# Main.net
KiCad netlist of a schematic drawn in Altium Designer
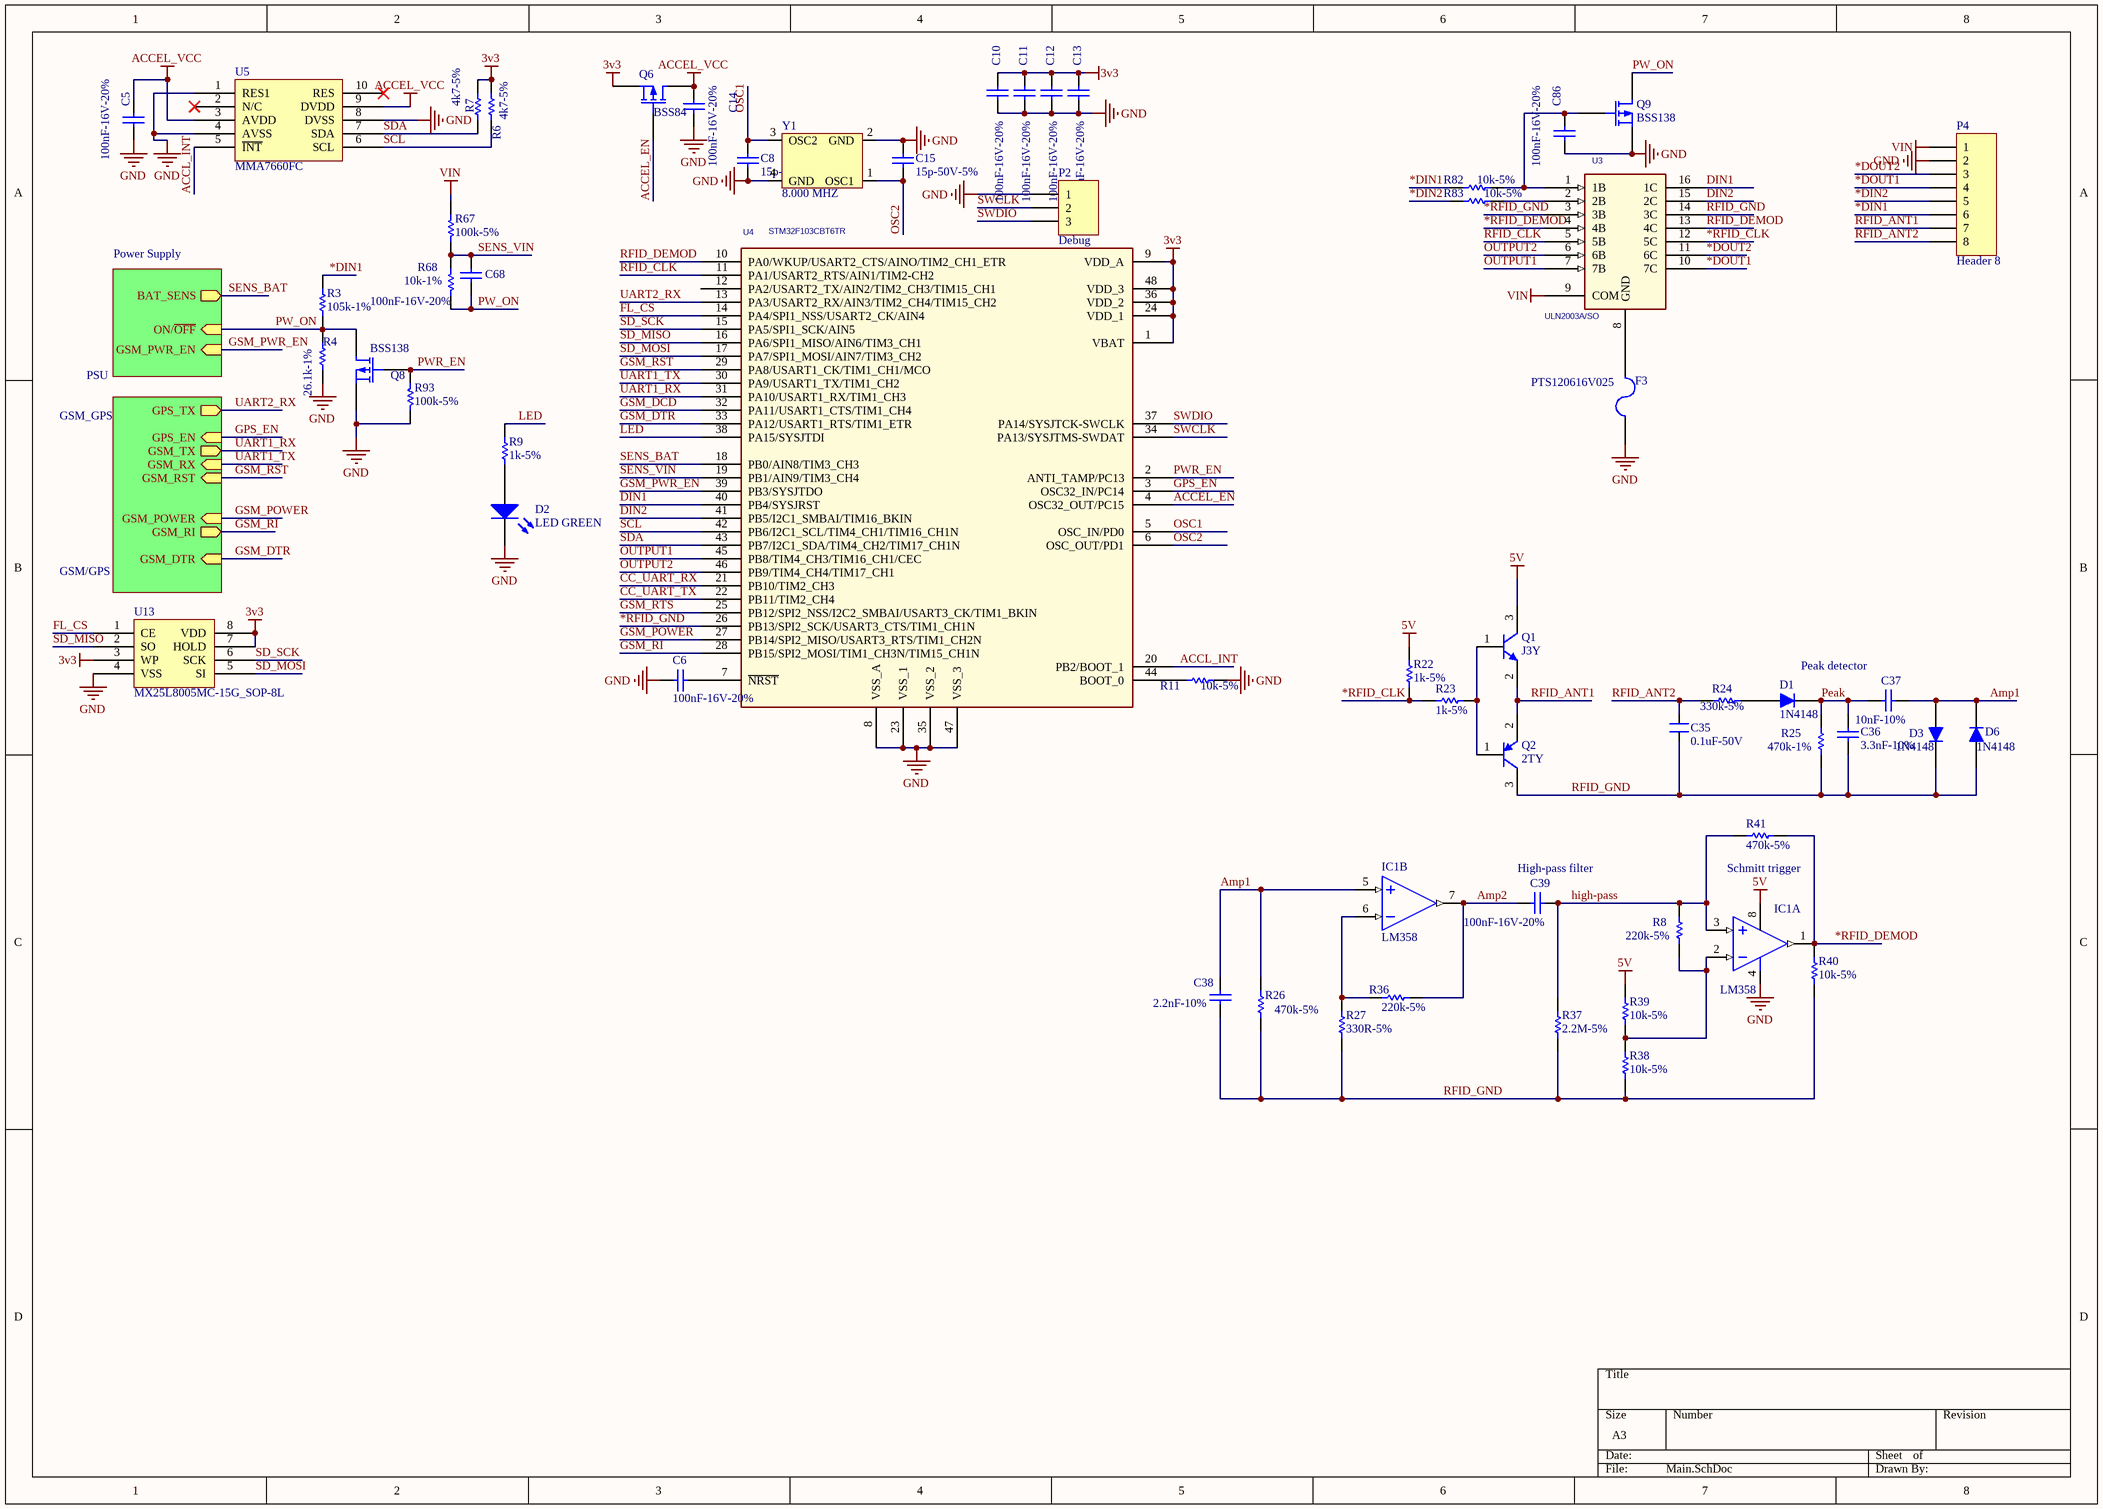
[diagram p0: Main.SchDoc]

(export (version "E")
  (design (tool "Eeschema 10.0.6"))
  (components
    (comp (ref "C5")
      (value "100nF-16V-20%")
      (footprint "C0402")
      (description "CAP CER 0.1UF 16V Y5V 0402")
      (fields
        (field (name "MANUFACTURER") "Yageo")
        (field (name "DIGI-KEY PART NUMBER") "311-1047-1-ND")
        (field (name "PUBLISHER") "Altium Limited")
      )
      (libsource (lib "Miscellaneous Devices") (part "Cap"))
    )
    (comp (ref "C6")
      (value "100nF-16V-20%")
      (footprint "C0402")
      (description "CAP CER 0.1UF 16V Y5V 0402")
      (fields
        (field (name "MANUFACTURER") "Yageo")
        (field (name "DIGI-KEY PART NUMBER") "311-1047-1-ND")
        (field (name "PUBLISHER") "Altium Limited")
      )
      (libsource (lib "Miscellaneous Devices") (part "Cap"))
    )
    (comp (ref "C8")
      (value "15p-50V-5%")
      (footprint "C0402")
      (description "CAP CER 15PF 50V 5% NPO 0402")
      (fields
        (field (name "MANUFACTURER") "Yageo")
        (field (name "DIGI-KEY PART NUMBER") "311-1017-1-ND")
        (field (name "PUBLISHER") "Altium Limited")
      )
      (libsource (lib "Miscellaneous Devices") (part "Cap"))
    )
    (comp (ref "C10")
      (value "100nF-16V-20%")
      (footprint "C0402")
      (description "CAP CER 0.1UF 16V Y5V 0402")
      (fields
        (field (name "MANUFACTURER") "Yageo")
        (field (name "DIGI-KEY PART NUMBER") "311-1047-1-ND")
        (field (name "PUBLISHER") "Altium Limited")
      )
      (libsource (lib "Miscellaneous Devices") (part "Cap"))
    )
    (comp (ref "C11")
      (value "100nF-16V-20%")
      (footprint "C0402")
      (description "CAP CER 0.1UF 16V Y5V 0402")
      (fields
        (field (name "MANUFACTURER") "Yageo")
        (field (name "DIGI-KEY PART NUMBER") "311-1047-1-ND")
        (field (name "PUBLISHER") "Altium Limited")
      )
      (libsource (lib "Miscellaneous Devices") (part "Cap"))
    )
    (comp (ref "C12")
      (value "100nF-16V-20%")
      (footprint "C0402")
      (description "CAP CER 0.1UF 16V Y5V 0402")
      (fields
        (field (name "MANUFACTURER") "Yageo")
        (field (name "DIGI-KEY PART NUMBER") "311-1047-1-ND")
        (field (name "PUBLISHER") "Altium Limited")
      )
      (libsource (lib "Miscellaneous Devices") (part "Cap"))
    )
    (comp (ref "C13")
      (value "100nF-16V-20%")
      (footprint "C0402")
      (description "CAP CER 0.1UF 16V Y5V 0402")
      (fields
        (field (name "MANUFACTURER") "Yageo")
        (field (name "DIGI-KEY PART NUMBER") "311-1047-1-ND")
        (field (name "PUBLISHER") "Altium Limited")
      )
      (libsource (lib "Miscellaneous Devices") (part "Cap"))
    )
    (comp (ref "C14")
      (value "100nF-16V-20%")
      (footprint "C0402")
      (description "CAP CER 0.1UF 16V Y5V 0402")
      (fields
        (field (name "MANUFACTURER") "Yageo")
        (field (name "DIGI-KEY PART NUMBER") "311-1047-1-ND")
        (field (name "PUBLISHER") "Altium Limited")
      )
      (libsource (lib "Miscellaneous Devices") (part "Cap"))
    )
    (comp (ref "C15")
      (value "15p-50V-5%")
      (footprint "C0402")
      (description "CAP CER 15PF 50V 5% NPO 0402")
      (fields
        (field (name "MANUFACTURER") "Yageo")
        (field (name "DIGI-KEY PART NUMBER") "311-1017-1-ND")
        (field (name "PUBLISHER") "Altium Limited")
      )
      (libsource (lib "Miscellaneous Devices") (part "Cap"))
    )
    (comp (ref "C35")
      (value "0.1uF-50V")
      (footprint "C0603")
      (description "CAP CER 0.1UF 50V Y5V 0603")
      (fields (field (name "DIGI-KEY PART NUMBER") "311-1343-2-ND") (field (name "MANUFACTURER") "Yageo"))
      (libsource (lib "syhaunguyen") (part "CN2"))
    )
    (comp (ref "C36")
      (value "3.3nF-10%")
      (footprint "C0402")
      (description "CAP CER 3300PF 50V 10% X7R 0402")
      (fields (field (name "DIGI-KEY PART NUMBER") "311-1034-2-ND") (field (name "MANUFACTURER") "Yageo"))
      (libsource (lib "Capacitor") (part "1nF-50V-C0805"))
    )
    (comp (ref "C37")
      (value "10nF-10%")
      (footprint "C0402")
      (description "Non-Polarized Capacitor")
      (fields (field (name "DIGI-KEY PART NUMBER") "CC0402KRX7R9BB103") (field (name "MANUFACTURER") "Yageo"))
      (libsource (lib "Capacitor") (part "10nF-50V-C0805"))
    )
    (comp (ref "C38")
      (value "2.2nF-10%")
      (footprint "C0402")
      (description "CAP CER 2200PF 50V 10% X7R 0402")
      (fields (field (name "DIGI-KEY PART NUMBER") "311-1037-2-ND") (field (name "MANUFACTURER") "Yageo"))
      (libsource (lib "Capacitor") (part "2.2nF-50V-C0805"))
    )
    (comp (ref "C39")
      (value "100nF-16V-20%")
      (footprint "C0402")
      (description "CAP CER 0.1UF 16V Y5V 0402")
      (fields
        (field (name "MANUFACTURER") "Yageo")
        (field (name "DIGI-KEY PART NUMBER") "311-1047-1-ND")
        (field (name "PUBLISHER") "Altium Limited")
      )
      (libsource (lib "Miscellaneous Devices") (part "Cap"))
    )
    (comp (ref "C68")
      (value "100nF-16V-20%")
      (footprint "C0402")
      (description "CAP CER 0.1UF 16V Y5V 0402")
      (fields
        (field (name "MANUFACTURER") "Yageo")
        (field (name "DIGI-KEY PART NUMBER") "311-1047-1-ND")
        (field (name "PUBLISHER") "Altium Limited")
      )
      (libsource (lib "Miscellaneous Devices") (part "Cap"))
    )
    (comp (ref "C86")
      (value "100nF-16V-20%")
      (footprint "C0402")
      (description "CAP CER 0.1UF 16V Y5V 0402")
      (fields
        (field (name "MANUFACTURER") "Yageo")
        (field (name "DIGI-KEY PART NUMBER") "311-1047-1-ND")
        (field (name "PUBLISHER") "Altium Limited")
      )
      (libsource (lib "Miscellaneous Devices") (part "Cap"))
    )
    (comp (ref "D1")
      (value "1N4148")
      (footprint "DO-213AA")
      (description "DIODE SMALL SIG 100V 0.2A ALF2")
      (fields
        (field (name "DIGI-KEY PART NUMBER") "568-1360-1-ND")
        (field (name "MANUFACTURER") "NXP Semiconductors")
      )
      (libsource (lib "Active Components") (part "1N4148"))
    )
    (comp (ref "D2")
      (value "LED GREEN")
      (footprint "LED0603-G")
      (description "LED GREEN CLEAR THIN 0603 SMD")
      (fields
        (field (name "DIGI-KEY PART NUMBER") "160-1446-2-ND")
        (field (name "MANUFACTURER") "Lite-On Inc")
        (field (name "PUBLISHER") "Altium Limited")
      )
      (libsource (lib "Miscellaneous Devices") (part "LED2"))
    )
    (comp (ref "D3")
      (value "1N4148")
      (footprint "DO-213AA")
      (description "DIODE SMALL SIG 100V 0.2A ALF2")
      (fields
        (field (name "DIGI-KEY PART NUMBER") "568-1360-1-ND")
        (field (name "MANUFACTURER") "NXP Semiconductors")
      )
      (libsource (lib "Active Components") (part "1N4148"))
    )
    (comp (ref "D6")
      (value "1N4148")
      (footprint "DO-213AA")
      (description "DIODE SMALL SIG 100V 0.2A ALF2")
      (fields
        (field (name "DIGI-KEY PART NUMBER") "568-1360-1-ND")
        (field (name "MANUFACTURER") "NXP Semiconductors")
      )
      (libsource (lib "Active Components") (part "1N4148"))
    )
    (comp (ref "F3")
      (value "PTS120616V025")
      (footprint "PTC1206")
      (description "PTC RESETTABLE SMD 1206 16V .25A")
      (fields
        (field (name "DIGI-KEY PART NUMBER") "283-3137-2-ND")
        (field (name "MANUFACTURER") "Cooper Bussmann")
        (field (name "PUBLISHER") "Altium Limited")
      )
      (libsource (lib "Miscellaneous Devices") (part "Fuse 2"))
    )
    (comp (ref "IC1")
      (value "LM358")
      (footprint "soic8")
      (description "Low-Power Dual Operational Amplifier")
      (libsource (lib "IC") (part "LM358"))
    )
    (comp (ref "P2")
      (value "Debug")
      (footprint "HEADER_1.27mm_3PIN")
      (description "NA")
      (fields (field (name "PUBLISHER") "Altium Limited"))
      (libsource (lib "Miscellaneous Connectors") (part "Header 3"))
    )
    (comp (ref "P4")
      (value "Header 8")
      (footprint "HDR1X8")
      (description "Header, 8-Pin")
      (fields (field (name "PUBLISHER") "Altium Limited"))
      (libsource (lib "Miscellaneous Connectors") (part "Header 8"))
    )
    (comp (ref "Q1")
      (value "J3Y")
      (footprint "SOT23_123")
      (description "NPN Bipolar Transistor")
      (libsource (lib "Active Components") (part "NPN_123"))
    )
    (comp (ref "Q2")
      (value "2TY")
      (footprint "SOT23_123")
      (description "PNP Bipolar Transistor")
      (libsource (lib "Active Components") (part "PNP_123"))
    )
    (comp (ref "Q6")
      (value "BSS84")
      (footprint "SOT23-3")
      (description "MOSFET P-CH 50V 130MA SOT23-3")
      (fields
        (field (name "DIGI-KEY PART NUMBER") "BSS84-FDITR-ND")
        (field (name "MANUFACTURER") "Diodes Inc")
        (field (name "PUBLISHER") "Altium Limited")
      )
      (libsource (lib "Miscellaneous Devices") (part "MOSFET-P"))
    )
    (comp (ref "Q8")
      (value "BSS138")
      (footprint "SOT23-3")
      (description "MOSFET N-CH 50V 200MA SOT23-3")
      (fields
        (field (name "DIGI-KEY PART NUMBER") "BSS138-FDICT-ND")
        (field (name "MANUFACTURER") "Diodes Inc")
        (field (name "PUBLISHER") "Altium Limited")
      )
      (libsource (lib "") (part "MOSFET-P_1"))
    )
    (comp (ref "Q9")
      (value "BSS138")
      (footprint "SOT23-3")
      (description "MOSFET N-CH 50V 200MA SOT23-3")
      (fields
        (field (name "DIGI-KEY PART NUMBER") "BSS138-FDICT-ND")
        (field (name "MANUFACTURER") "Diodes Inc")
        (field (name "PUBLISHER") "Altium Limited")
      )
      (libsource (lib "") (part "MOSFET-P_1"))
    )
    (comp (ref "R3")
      (value "105k-1%")
      (footprint "R0402")
      (description "RES 105k OHM 1/4W 1% 0805 SMD")
      (fields (field (name "DIGI-KEY PART NUMBER") "311-105KCRTR-ND") (field (name "MANUFACTURER") "Yageo"))
      (libsource (lib "All_Resistor") (part "105k-1%-R0805"))
    )
    (comp (ref "R4")
      (value "26.1k-1%")
      (footprint "R0402")
      (description "RES 26.1k OHM 1/4W 1% 0805 SMD")
      (fields (field (name "DIGI-KEY PART NUMBER") "311-26.1KCRTR-ND") (field (name "MANUFACTURER") "Yageo"))
      (libsource (lib "All_Resistor") (part "26.1k-1%-R0805"))
    )
    (comp (ref "R6")
      (value "4k7-5%")
      (footprint "R0402")
      (description "RES 4.7K OHM 1/16W 5% 0402 SMD")
      (fields
        (field (name "DIGI-KEY PART NUMBER") "311-4.7KJRCT-ND")
        (field (name "MANUFACTURER") "Yageo")
        (field (name "PUBLISHER") "Altium Limited")
      )
      (libsource (lib "Miscellaneous Devices") (part "Res1"))
    )
    (comp (ref "R7")
      (value "4k7-5%")
      (footprint "R0402")
      (description "RES 4.7K OHM 1/16W 5% 0402 SMD")
      (fields
        (field (name "DIGI-KEY PART NUMBER") "311-4.7KJRCT-ND")
        (field (name "MANUFACTURER") "Yageo")
        (field (name "PUBLISHER") "Altium Limited")
      )
      (libsource (lib "Miscellaneous Devices") (part "Res1"))
    )
    (comp (ref "R8")
      (value "220k-5%")
      (footprint "R0402")
      (description "RES 220k OHM 1/8W 5% 0805 SMD")
      (fields (field (name "DIGI-KEY PART NUMBER") "311-220KARTR-ND") (field (name "MANUFACTURER") "Yageo"))
      (libsource (lib "Resistor") (part "220k-5%-R0805"))
    )
    (comp (ref "R9")
      (value "1k-5%")
      (footprint "R0402")
      (description "RES 1.0K OHM 1/16W 5% 0402 SMD")
      (fields
        (field (name "DIGI-KEY PART NUMBER") "311-1.0KJRCT-ND")
        (field (name "MANUFACTURER") "Yageo")
        (field (name "PUBLISHER") "Altium Limited")
      )
      (libsource (lib "Miscellaneous Devices") (part "Res1"))
    )
    (comp (ref "R11")
      (value "10k-5%")
      (footprint "R0402")
      (description "RES 10K OHM 1/16W 5% 0402 SMD")
      (fields
        (field (name "DIGI-KEY PART NUMBER") "311-10KJRCT-ND")
        (field (name "MANUFACTURER") "Yageo")
        (field (name "PUBLISHER") "Altium Limited")
      )
      (libsource (lib "Miscellaneous Devices") (part "Res1"))
    )
    (comp (ref "R22")
      (value "1k-5%")
      (footprint "R0402")
      (description "RES 1k OHM 1/8W 5% 0805 SMD")
      (fields (field (name "DIGI-KEY PART NUMBER") "311-1.0KARTR-ND") (field (name "MANUFACTURER") "Yageo"))
      (libsource (lib "All_Resistor") (part "1k-5%-R0805"))
    )
    (comp (ref "R23")
      (value "1k-5%")
      (footprint "R0402")
      (description "RES 1k OHM 1/8W 5% 0805 SMD")
      (fields (field (name "DIGI-KEY PART NUMBER") "311-1.0KARTR-ND") (field (name "MANUFACTURER") "Yageo"))
      (libsource (lib "All_Resistor") (part "1k-5%-R0805"))
    )
    (comp (ref "R24")
      (value "330k-5%")
      (footprint "R0402")
      (description "RES 330k OHM 1/8W 5% 0805 SMD")
      (fields (field (name "DIGI-KEY PART NUMBER") "311-330KARTR-ND") (field (name "MANUFACTURER") "Yageo"))
      (libsource (lib "Resistor") (part "330k-5%-R0805"))
    )
    (comp (ref "R25")
      (value "470k-1%")
      (footprint "R0402")
      (description "RES 470k OHM 1/4W 1% 0805 SMD")
      (fields (field (name "DIGI-KEY PART NUMBER") "311-470KCRTR-ND") (field (name "MANUFACTURER") "Yageo"))
      (libsource (lib "Resistor") (part "470k-1%-R0805"))
    )
    (comp (ref "R26")
      (value "470k-5%")
      (footprint "R0402")
      (description "RES 470k OHM 1/8W 5% 0805 SMD")
      (fields (field (name "DIGI-KEY PART NUMBER") "311-470KARTR-ND") (field (name "MANUFACTURER") "Yageo"))
      (libsource (lib "Resistor") (part "470k-5%-R0805"))
    )
    (comp (ref "R27")
      (value "330R-5%")
      (footprint "R0402")
      (description "RES 330 OHM 1/8W 5% 0805 SMD")
      (fields (field (name "DIGI-KEY PART NUMBER") "311-330ARTR-ND") (field (name "MANUFACTURER") "Yageo"))
      (libsource (lib "Resistor") (part "330R-5%-R0805"))
    )
    (comp (ref "R36")
      (value "220k-5%")
      (footprint "R0402")
      (description "RES 220k OHM 1/8W 5% 0805 SMD")
      (fields (field (name "DIGI-KEY PART NUMBER") "311-220KARTR-ND") (field (name "MANUFACTURER") "Yageo"))
      (libsource (lib "Resistor") (part "220k-5%-R0805"))
    )
    (comp (ref "R37")
      (value "2.2M-5%")
      (footprint "R0402")
      (description "RES 2.2M OHM 1/8W 5% 0805 SMD")
      (fields (field (name "DIGI-KEY PART NUMBER") "311-2.2MARTR-ND") (field (name "MANUFACTURER") "Yageo"))
      (libsource (lib "Resistor") (part "2.2M-5%-R0805"))
    )
    (comp (ref "R38")
      (value "10k-5%")
      (footprint "R0402")
      (description "RES 10k OHM 1/8W 5% 0805 SMD")
      (fields (field (name "DIGI-KEY PART NUMBER") "311-10KARTR-ND") (field (name "MANUFACTURER") "Yageo"))
      (libsource (lib "Resistor") (part "10k-5%-R0805"))
    )
    (comp (ref "R39")
      (value "10k-5%")
      (footprint "R0402")
      (description "RES 10k OHM 1/8W 5% 0805 SMD")
      (fields (field (name "DIGI-KEY PART NUMBER") "311-10KARTR-ND") (field (name "MANUFACTURER") "Yageo"))
      (libsource (lib "Resistor") (part "10k-5%-R0805"))
    )
    (comp (ref "R40")
      (value "10k-5%")
      (footprint "R0402")
      (description "RES 10k OHM 1/8W 5% 0805 SMD")
      (fields (field (name "DIGI-KEY PART NUMBER") "311-10KARTR-ND") (field (name "MANUFACTURER") "Yageo"))
      (libsource (lib "Resistor") (part "10k-5%-R0805"))
    )
    (comp (ref "R41")
      (value "470k-5%")
      (footprint "R0402")
      (description "RES 470k OHM 1/8W 5% 0805 SMD")
      (fields (field (name "DIGI-KEY PART NUMBER") "311-470KARTR-ND") (field (name "MANUFACTURER") "Yageo"))
      (libsource (lib "Resistor") (part "470k-5%-R0805"))
    )
    (comp (ref "R67")
      (value "100k-5%")
      (footprint "R0402")
      (description "RES 100K OHM 1/16W 5% 0402 SMD")
      (fields
        (field (name "DIGI-KEY PART NUMBER") "311-100KJRCT-ND")
        (field (name "MANUFACTURER") "Yageo")
        (field (name "PUBLISHER") "Altium Limited")
      )
      (libsource (lib "Miscellaneous Devices") (part "Res1"))
    )
    (comp (ref "R68")
      (value "10k-1%")
      (footprint "R0402")
      (description "RES 10.0K OHM 1/16W 1% 0402 SMD")
      (fields
        (field (name "DIGI-KEY PART NUMBER") "311-10.0KLRTR-ND")
        (field (name "MANUFACTURER") "Yageo")
        (field (name "PUBLISHER") "Altium Limited")
      )
      (libsource (lib "Miscellaneous Devices") (part "Res1"))
    )
    (comp (ref "R82")
      (value "10k-5%")
      (footprint "R0402")
      (description "RES 10K OHM 1/16W 5% 0402 SMD")
      (fields
        (field (name "DIGI-KEY PART NUMBER") "311-10KJRCT-ND")
        (field (name "MANUFACTURER") "Yageo")
        (field (name "PUBLISHER") "Altium Limited")
      )
      (libsource (lib "Miscellaneous Devices") (part "Res1"))
    )
    (comp (ref "R83")
      (value "10k-5%")
      (footprint "R0402")
      (description "RES 10K OHM 1/16W 5% 0402 SMD")
      (fields
        (field (name "DIGI-KEY PART NUMBER") "311-10KJRCT-ND")
        (field (name "MANUFACTURER") "Yageo")
        (field (name "PUBLISHER") "Altium Limited")
      )
      (libsource (lib "Miscellaneous Devices") (part "Res1"))
    )
    (comp (ref "R93")
      (value "100k-5%")
      (footprint "R0402")
      (description "RES 100K OHM 1/16W 5% 0402 SMD")
      (fields
        (field (name "DIGI-KEY PART NUMBER") "311-100KJRCT-ND")
        (field (name "MANUFACTURER") "Yageo")
        (field (name "PUBLISHER") "Altium Limited")
      )
      (libsource (lib "Miscellaneous Devices") (part "Res1"))
    )
    (comp (ref "U3")
      (value "ULN2003A/SO")
      (footprint "SO16-150mil")
      (description "IC DARL TRANS ARRAY 16-SOIC")
      (fields
        (field (name "DIGI-KEY PART NUMBER") "296-1368-2-ND")
        (field (name "MANUFACTURER PART NUMBER") "ULN2003ADR")
      )
      (libsource (lib "*") (part "ULN2003A/SO_0"))
    )
    (comp (ref "U4")
      (value "STM32F103CBT6TR")
      (footprint "TQFP-48-P0.5")
      (description "MCU ARM 128K FLASH/TIMER")
      (fields
        (field (name "DIGI-KEY PART NUMBER") "497-6288-ND")
        (field (name "MANUFACTURER") "STMicroelectronics")
      )
      (libsource (lib "*") (part "ATmega128_4"))
    )
    (comp (ref "U5")
      (value "MMA7660FC")
      (footprint "MMA7660FC")
      (description "ACCELEROMETER 3X3 DGTL 10-DFN")
      (fields
        (field (name "DIGI-KEY PART NUMBER") "MMA7660FCT-ND")
        (field (name "MANUFACTURER") "Freescale Semiconductor")
      )
      (libsource (lib "Lib") (part "MMA7660FC"))
    )
    (comp (ref "U13")
      (value "MX25L8005MC-15G_SOP-8L")
      (footprint "SO8-200mil")
      (fields (field (name "MANUFACTURER") "Tyrone"))
      (libsource (lib "My LB") (part "FlashIC"))
    )
    (comp (ref "Y1")
      (value "8.000 MHZ")
      (footprint "SMD CRYSTAL 4 x 2.5")
      (description "CRYSTAL 8.000 MHZ 18PF SMD")
      (fields
        (field (name "DIGI-KEY PART NUMBER") "887-1452-2-ND")
        (field (name "MANUFACTURER") "TXC CORPORATION")
      )
      (libsource (lib "Schlib1") (part "CRYSTAL-SMT"))
    )
  )
  (nets
    (net (code "1") (name "/*DIN1") (class "Default")
      (node (ref "P4") (pin "6") (pinfunction "6_6") (pintype "passive"))
      (node (ref "R3") (pin "2") (pinfunction "2_2") (pintype "passive"))
      (node (ref "R82") (pin "1") (pinfunction "1_1") (pintype "passive"))
    )
    (net (code "2") (name "/*DIN2") (class "Default")
      (node (ref "P4") (pin "5") (pinfunction "5_5") (pintype "passive"))
      (node (ref "R83") (pin "2") (pinfunction "2_2") (pintype "passive"))
    )
    (net (code "3") (name "/*DOUT1") (class "Default")
      (node (ref "P4") (pin "4") (pinfunction "4_4") (pintype "passive"))
      (node (ref "U3") (pin "10") (pinfunction "7C_10") (pintype "open_collector"))
    )
    (net (code "4") (name "/*DOUT2") (class "Default")
      (node (ref "P4") (pin "3") (pinfunction "3_3") (pintype "passive"))
      (node (ref "U3") (pin "11") (pinfunction "6C_11") (pintype "open_collector"))
    )
    (net (code "5") (name "/*RFID_CLK") (class "Default")
      (node (ref "R22") (pin "1") (pinfunction "1_1") (pintype "passive"))
      (node (ref "R23") (pin "2") (pinfunction "2_2") (pintype "passive"))
      (node (ref "U3") (pin "12") (pinfunction "5C_12") (pintype "open_collector"))
    )
    (net (code "6") (name "/*RFID_DEMOD") (class "Default")
      (node (ref "IC1") (pin "1") (pinfunction "OUT_1") (pintype "output"))
      (node (ref "R40") (pin "2") (pinfunction "2_2") (pintype "passive"))
      (node (ref "R41") (pin "1") (pinfunction "1_1") (pintype "passive"))
      (node (ref "U3") (pin "4") (pinfunction "4B_4") (pintype "input"))
    )
    (net (code "7") (name "/*RFID_GND") (class "Default")
      (node (ref "U3") (pin "3") (pinfunction "3B_3") (pintype "input"))
      (node (ref "U4") (pin "26") (pinfunction "PB13/SPI2_SCK/USART3_CTS/TIM1_CH1N_26") (pintype "passive"))
    )
    (net (code "8") (name "/ACCEL_EN") (class "Default")
      (node (ref "Q6") (pin "1") (pinfunction "G_1") (pintype "passive"))
      (node (ref "U4") (pin "4") (pinfunction "OSC32_OUT/PC15_4") (pintype "passive"))
    )
    (net (code "9") (name "/ACCL_INT") (class "Default")
      (node (ref "U4") (pin "20") (pinfunction "PB2/BOOT_1_20") (pintype "passive"))
      (node (ref "U5") (pin "5") (pinfunction "~{INT}_5") (pintype "passive"))
    )
    (net (code "10") (name "/Amp1") (class "Default")
      (node (ref "C37") (pin "2") (pinfunction "2_2") (pintype "passive"))
      (node (ref "C38") (pin "2") (pinfunction "2_2") (pintype "passive"))
      (node (ref "D3") (pin "1") (pinfunction "A_1") (pintype "passive"))
      (node (ref "D6") (pin "2") (pinfunction "K_2") (pintype "passive"))
      (node (ref "IC1") (pin "5") (pinfunction "IN+_5") (pintype "input"))
      (node (ref "R26") (pin "1") (pinfunction "1_1") (pintype "passive"))
    )
    (net (code "11") (name "/Amp2") (class "Default")
      (node (ref "C39") (pin "2") (pinfunction "2_2") (pintype "passive"))
      (node (ref "IC1") (pin "7") (pinfunction "OUT_7") (pintype "output"))
      (node (ref "R36") (pin "1") (pinfunction "1_1") (pintype "passive"))
    )
    (net (code "12") (name "/CC_UART_RX") (class "Default")
      (node (ref "U4") (pin "21") (pinfunction "PB10/TIM2_CH3_21") (pintype "passive"))
    )
    (net (code "13") (name "/CC_UART_TX") (class "Default")
      (node (ref "U4") (pin "22") (pinfunction "PB11/TIM2_CH4_22") (pintype "passive"))
    )
    (net (code "14") (name "/DIN1") (class "Default")
      (node (ref "U3") (pin "16") (pinfunction "1C_16") (pintype "open_collector"))
      (node (ref "U4") (pin "40") (pinfunction "PB4/SYSJRST_40") (pintype "passive"))
    )
    (net (code "15") (name "/DIN2") (class "Default")
      (node (ref "U3") (pin "15") (pinfunction "2C_15") (pintype "open_collector"))
      (node (ref "U4") (pin "41") (pinfunction "PB5/I2C1_SMBAI/TIM16_BKIN_41") (pintype "passive"))
    )
    (net (code "16") (name "/FL_CS") (class "Default")
      (node (ref "U13") (pin "1") (pinfunction "CE_1") (pintype "passive"))
      (node (ref "U4") (pin "14") (pinfunction "PA4/SPI1_NSS/USART2_CK/AIN4_14") (pintype "passive"))
    )
    (net (code "17") (name "/GPS_EN") (class "Default")
      (node (ref "U4") (pin "3") (pinfunction "OSC32_IN/PC14_3") (pintype "passive"))
    )
    (net (code "18") (name "/GSM_DCD") (class "Default")
      (node (ref "U4") (pin "32") (pinfunction "PA11/USART1_CTS/TIM1_CH4_32") (pintype "passive"))
    )
    (net (code "19") (name "/GSM_DTR") (class "Default")
      (node (ref "U4") (pin "33") (pinfunction "PA12/USART1_RTS/TIM1_ETR_33") (pintype "passive"))
    )
    (net (code "20") (name "/GSM_POWER") (class "Default")
      (node (ref "U4") (pin "27") (pinfunction "PB14/SPI2_MISO/USART3_RTS/TIM1_CH2N_27") (pintype "passive"))
    )
    (net (code "21") (name "/GSM_PWR_EN") (class "Default")
      (node (ref "U4") (pin "39") (pinfunction "PB3/SYSJTDO_39") (pintype "passive"))
    )
    (net (code "22") (name "/GSM_RI") (class "Default")
      (node (ref "U4") (pin "28") (pinfunction "PB15/SPI2_MOSI/TIM1_CH3N/TIM15_CH1N_28") (pintype "passive"))
    )
    (net (code "23") (name "/GSM_RST") (class "Default")
      (node (ref "U4") (pin "29") (pinfunction "PA8/USART1_CK/TIM1_CH1/MCO_29") (pintype "passive"))
    )
    (net (code "24") (name "/GSM_RTS") (class "Default")
      (node (ref "U4") (pin "25") (pinfunction "PB12/SPI2_NSS/I2C2_SMBAI/USART3_CK/TIM1_BKIN_25") (pintype "passive"))
    )
    (net (code "25") (name "/LED") (class "Default")
      (node (ref "R9") (pin "2") (pinfunction "2_2") (pintype "passive"))
      (node (ref "U4") (pin "38") (pinfunction "PA15/SYSJTDI_38") (pintype "passive"))
    )
    (net (code "26") (name "/OSC1") (class "Default")
      (node (ref "C8") (pin "2") (pinfunction "2_2") (pintype "passive"))
      (node (ref "U4") (pin "5") (pinfunction "OSC_IN/PD0_5") (pintype "passive"))
      (node (ref "Y1") (pin "3") (pinfunction "OSC2_3") (pintype "passive"))
    )
    (net (code "27") (name "/OSC2") (class "Default")
      (node (ref "C15") (pin "1") (pinfunction "1_1") (pintype "passive"))
      (node (ref "U4") (pin "6") (pinfunction "OSC_OUT/PD1_6") (pintype "passive"))
      (node (ref "Y1") (pin "1") (pinfunction "OSC1_1") (pintype "passive"))
    )
    (net (code "28") (name "/OUTPUT1") (class "Default")
      (node (ref "U3") (pin "7") (pinfunction "7B_7") (pintype "input"))
      (node (ref "U4") (pin "45") (pinfunction "PB8/TIM4_CH3/TIM16_CH1/CEC_45") (pintype "passive"))
    )
    (net (code "29") (name "/OUTPUT2") (class "Default")
      (node (ref "U3") (pin "6") (pinfunction "6B_6") (pintype "input"))
      (node (ref "U4") (pin "46") (pinfunction "PB9/TIM4_CH4/TIM17_CH1_46") (pintype "passive"))
    )
    (net (code "30") (name "/PWR_EN") (class "Default")
      (node (ref "Q8") (pin "1") (pinfunction "G_1") (pintype "passive"))
      (node (ref "R93") (pin "1") (pinfunction "1_1") (pintype "passive"))
      (node (ref "U4") (pin "2") (pinfunction "ANTI_TAMP/PC13_2") (pintype "passive"))
    )
    (net (code "31") (name "/PW_ON") (class "Default")
      (node (ref "C68") (pin "1") (pinfunction "1_1") (pintype "passive"))
      (node (ref "Q8") (pin "3") (pinfunction "D_3") (pintype "passive"))
      (node (ref "Q9") (pin "3") (pinfunction "D_3") (pintype "passive"))
      (node (ref "R3") (pin "1") (pinfunction "1_1") (pintype "passive"))
      (node (ref "R4") (pin "2") (pinfunction "2_2") (pintype "passive"))
      (node (ref "R68") (pin "1") (pinfunction "1_1") (pintype "passive"))
    )
    (net (code "32") (name "/Peak") (class "Default")
      (node (ref "C36") (pin "1") (pinfunction "1_1") (pintype "passive"))
      (node (ref "C37") (pin "1") (pinfunction "1_1") (pintype "passive"))
      (node (ref "D1") (pin "2") (pinfunction "K_2") (pintype "passive"))
      (node (ref "R25") (pin "1") (pinfunction "1_1") (pintype "passive"))
    )
    (net (code "33") (name "/RFID_ANT1") (class "Default")
      (node (ref "P4") (pin "7") (pinfunction "7_7") (pintype "passive"))
      (node (ref "Q1") (pin "2") (pinfunction "E_2") (pintype "passive"))
      (node (ref "Q2") (pin "2") (pinfunction "E_2") (pintype "passive"))
    )
    (net (code "34") (name "/RFID_ANT2") (class "Default")
      (node (ref "C35") (pin "2") (pinfunction "2_2") (pintype "passive"))
      (node (ref "P4") (pin "8") (pinfunction "8_8") (pintype "passive"))
      (node (ref "R24") (pin "2") (pinfunction "2_2") (pintype "passive"))
    )
    (net (code "35") (name "/RFID_CLK") (class "Default")
      (node (ref "U3") (pin "5") (pinfunction "5B_5") (pintype "input"))
      (node (ref "U4") (pin "11") (pinfunction "PA1/USART2_RTS/AIN1/TIM2-CH2_11") (pintype "passive"))
    )
    (net (code "36") (name "/RFID_DEMOD") (class "Default")
      (node (ref "U3") (pin "13") (pinfunction "4C_13") (pintype "open_collector"))
      (node (ref "U4") (pin "10") (pinfunction "PA0/WKUP/USART2_CTS/AINO/TIM2_CH1_ETR_10") (pintype "passive"))
    )
    (net (code "37") (name "/RFID_GND") (class "Default")
      (node (ref "C35") (pin "1") (pinfunction "1_1") (pintype "passive"))
      (node (ref "C36") (pin "2") (pinfunction "2_2") (pintype "passive"))
      (node (ref "C38") (pin "1") (pinfunction "1_1") (pintype "passive"))
      (node (ref "D3") (pin "2") (pinfunction "K_2") (pintype "passive"))
      (node (ref "D6") (pin "1") (pinfunction "A_1") (pintype "passive"))
      (node (ref "Q2") (pin "3") (pinfunction "C_3") (pintype "passive"))
      (node (ref "R25") (pin "2") (pinfunction "2_2") (pintype "passive"))
      (node (ref "R26") (pin "2") (pinfunction "2_2") (pintype "passive"))
      (node (ref "R27") (pin "1") (pinfunction "1_1") (pintype "passive"))
      (node (ref "R37") (pin "1") (pinfunction "1_1") (pintype "passive"))
      (node (ref "R38") (pin "2") (pinfunction "2_2") (pintype "passive"))
      (node (ref "R40") (pin "1") (pinfunction "1_1") (pintype "passive"))
      (node (ref "U3") (pin "14") (pinfunction "3C_14") (pintype "open_collector"))
    )
    (net (code "38") (name "/SCL") (class "Default")
      (node (ref "R6") (pin "1") (pinfunction "1_1") (pintype "passive"))
      (node (ref "U4") (pin "42") (pinfunction "PB6/I2C1_SCL/TIM4_CH1/TIM16_CH1N_42") (pintype "passive"))
      (node (ref "U5") (pin "6") (pinfunction "SCL_6") (pintype "passive"))
    )
    (net (code "39") (name "/SDA") (class "Default")
      (node (ref "R7") (pin "1") (pinfunction "1_1") (pintype "passive"))
      (node (ref "U4") (pin "43") (pinfunction "PB7/I2C1_SDA/TIM4_CH2/TIM17_CH1N_43") (pintype "passive"))
      (node (ref "U5") (pin "7") (pinfunction "SDA_7") (pintype "passive"))
    )
    (net (code "40") (name "/SD_MISO") (class "Default")
      (node (ref "U13") (pin "2") (pinfunction "SO_2") (pintype "passive"))
      (node (ref "U4") (pin "16") (pinfunction "PA6/SPI1_MISO/AIN6/TIM3_CH1_16") (pintype "passive"))
    )
    (net (code "41") (name "/SD_MOSI") (class "Default")
      (node (ref "U13") (pin "5") (pinfunction "SI_5") (pintype "passive"))
      (node (ref "U4") (pin "17") (pinfunction "PA7/SPI1_MOSI/AIN7/TIM3_CH2_17") (pintype "passive"))
    )
    (net (code "42") (name "/SD_SCK") (class "Default")
      (node (ref "U13") (pin "6") (pinfunction "SCK_6") (pintype "passive"))
      (node (ref "U4") (pin "15") (pinfunction "PA5/SPI1_SCK/AIN5_15") (pintype "passive"))
    )
    (net (code "43") (name "/SENS_BAT") (class "Default")
      (node (ref "U4") (pin "18") (pinfunction "PB0/AIN8/TIM3_CH3_18") (pintype "passive"))
    )
    (net (code "44") (name "/SENS_VIN") (class "Default")
      (node (ref "C68") (pin "2") (pinfunction "2_2") (pintype "passive"))
      (node (ref "R67") (pin "2") (pinfunction "2_2") (pintype "passive"))
      (node (ref "R68") (pin "2") (pinfunction "2_2") (pintype "passive"))
      (node (ref "U4") (pin "19") (pinfunction "PB1/AIN9/TIM3_CH4_19") (pintype "passive"))
    )
    (net (code "45") (name "/SWCLK") (class "Default")
      (node (ref "P2") (pin "2") (pinfunction "2_2") (pintype "passive"))
      (node (ref "U4") (pin "34") (pinfunction "PA13/SYSJTMS-SWDAT_34") (pintype "passive"))
    )
    (net (code "46") (name "/SWDIO") (class "Default")
      (node (ref "P2") (pin "3") (pinfunction "3_3") (pintype "passive"))
      (node (ref "U4") (pin "37") (pinfunction "PA14/SYSJTCK-SWCLK_37") (pintype "passive"))
    )
    (net (code "47") (name "/UART1_RX") (class "Default")
      (node (ref "U4") (pin "31") (pinfunction "PA10/USART1_RX/TIM1_CH3_31") (pintype "passive"))
    )
    (net (code "48") (name "/UART1_TX") (class "Default")
      (node (ref "U4") (pin "30") (pinfunction "PA9/USART1_TX/TIM1_CH2_30") (pintype "passive"))
    )
    (net (code "49") (name "/UART2_RX") (class "Default")
      (node (ref "U4") (pin "13") (pinfunction "PA3/USART2_RX/AIN3/TIM2_CH4/TIM15_CH2_13") (pintype "passive"))
    )
    (net (code "50") (name "/high-pass") (class "Default")
      (node (ref "C39") (pin "1") (pinfunction "1_1") (pintype "passive"))
      (node (ref "IC1") (pin "3") (pinfunction "IN+_3") (pintype "input"))
      (node (ref "R37") (pin "2") (pinfunction "2_2") (pintype "passive"))
      (node (ref "R41") (pin "2") (pinfunction "2_2") (pintype "passive"))
      (node (ref "R8") (pin "2") (pinfunction "2_2") (pintype "passive"))
    )
    (net (code "51") (name "3v3") (class "Default")
      (node (ref "C10") (pin "1") (pinfunction "1_1") (pintype "passive"))
      (node (ref "C11") (pin "1") (pinfunction "1_1") (pintype "passive"))
      (node (ref "C12") (pin "1") (pinfunction "1_1") (pintype "passive"))
      (node (ref "C13") (pin "1") (pinfunction "1_1") (pintype "passive"))
      (node (ref "Q6") (pin "2") (pinfunction "S_2") (pintype "passive"))
      (node (ref "R6") (pin "2") (pinfunction "2_2") (pintype "passive"))
      (node (ref "R7") (pin "2") (pinfunction "2_2") (pintype "passive"))
      (node (ref "U13") (pin "3") (pinfunction "WP_3") (pintype "passive"))
      (node (ref "U13") (pin "7") (pinfunction "HOLD_7") (pintype "passive"))
      (node (ref "U13") (pin "8") (pinfunction "VDD_8") (pintype "passive"))
      (node (ref "U4") (pin "1") (pinfunction "VBAT_1") (pintype "passive"))
      (node (ref "U4") (pin "24") (pinfunction "VDD_1_24") (pintype "passive"))
      (node (ref "U4") (pin "36") (pinfunction "VDD_2_36") (pintype "passive"))
      (node (ref "U4") (pin "48") (pinfunction "VDD_3_48") (pintype "passive"))
      (node (ref "U4") (pin "9") (pinfunction "VDD_A_9") (pintype "passive"))
    )
    (net (code "52") (name "5V") (class "Default")
      (node (ref "IC1") (pin "8") (pinfunction "+V_8") (pintype "passive"))
      (node (ref "Q1") (pin "3") (pinfunction "C_3") (pintype "passive"))
      (node (ref "R22") (pin "2") (pinfunction "2_2") (pintype "passive"))
      (node (ref "R39") (pin "1") (pinfunction "1_1") (pintype "passive"))
    )
    (net (code "53") (name "ACCEL_VCC") (class "Default")
      (node (ref "C14") (pin "2") (pinfunction "2_2") (pintype "passive"))
      (node (ref "C5") (pin "2") (pinfunction "2_2") (pintype "passive"))
      (node (ref "Q6") (pin "3") (pinfunction "D_3") (pintype "passive"))
      (node (ref "U5") (pin "3") (pinfunction "AVDD_3") (pintype "passive"))
      (node (ref "U5") (pin "9") (pinfunction "DVDD_9") (pintype "passive"))
    )
    (net (code "54") (name "GND") (class "Default")
      (node (ref "C10") (pin "2") (pinfunction "2_2") (pintype "passive"))
      (node (ref "C11") (pin "2") (pinfunction "2_2") (pintype "passive"))
      (node (ref "C12") (pin "2") (pinfunction "2_2") (pintype "passive"))
      (node (ref "C13") (pin "2") (pinfunction "2_2") (pintype "passive"))
      (node (ref "C14") (pin "1") (pinfunction "1_1") (pintype "passive"))
      (node (ref "C15") (pin "2") (pinfunction "2_2") (pintype "passive"))
      (node (ref "C5") (pin "1") (pinfunction "1_1") (pintype "passive"))
      (node (ref "C6") (pin "2") (pinfunction "2_2") (pintype "passive"))
      (node (ref "C8") (pin "1") (pinfunction "1_1") (pintype "passive"))
      (node (ref "C86") (pin "1") (pinfunction "1_1") (pintype "passive"))
      (node (ref "D2") (pin "2") (pinfunction "K_2") (pintype "passive"))
      (node (ref "F3") (pin "2") (pinfunction "2_2") (pintype "passive"))
      (node (ref "IC1") (pin "4") (pinfunction "-V_4") (pintype "passive"))
      (node (ref "P2") (pin "1") (pinfunction "1_1") (pintype "passive"))
      (node (ref "P4") (pin "2") (pinfunction "2_2") (pintype "passive"))
      (node (ref "Q8") (pin "2") (pinfunction "S_2") (pintype "passive"))
      (node (ref "Q9") (pin "2") (pinfunction "S_2") (pintype "passive"))
      (node (ref "R11") (pin "1") (pinfunction "1_1") (pintype "passive"))
      (node (ref "R4") (pin "1") (pinfunction "1_1") (pintype "passive"))
      (node (ref "R93") (pin "2") (pinfunction "2_2") (pintype "passive"))
      (node (ref "U13") (pin "4") (pinfunction "VSS_4") (pintype "passive"))
      (node (ref "U4") (pin "23") (pinfunction "VSS_1_23") (pintype "passive"))
      (node (ref "U4") (pin "35") (pinfunction "VSS_2_35") (pintype "passive"))
      (node (ref "U4") (pin "47") (pinfunction "VSS_3_47") (pintype "passive"))
      (node (ref "U4") (pin "8") (pinfunction "VSS_A_8") (pintype "passive"))
      (node (ref "U5") (pin "1") (pinfunction "RES1_1") (pintype "passive"))
      (node (ref "U5") (pin "4") (pinfunction "AVSS_4") (pintype "passive"))
      (node (ref "U5") (pin "8") (pinfunction "DVSS_8") (pintype "passive"))
      (node (ref "Y1") (pin "2") (pinfunction "GND_2") (pintype "passive"))
      (node (ref "Y1") (pin "4") (pinfunction "GND_4") (pintype "passive"))
    )
    (net (code "55") (name "Net-(D1-A)") (class "Default")
      (node (ref "D1") (pin "1") (pinfunction "A_1") (pintype "passive"))
      (node (ref "R24") (pin "1") (pinfunction "1_1") (pintype "passive"))
    )
    (net (code "56") (name "Net-(D2-A)") (class "Default")
      (node (ref "D2") (pin "1") (pinfunction "A_1") (pintype "passive"))
      (node (ref "R9") (pin "1") (pinfunction "1_1") (pintype "passive"))
    )
    (net (code "57") (name "Net-(IC1A-IN-)") (class "Default")
      (node (ref "IC1") (pin "2") (pinfunction "IN-_2") (pintype "input"))
      (node (ref "R38") (pin "1") (pinfunction "1_1") (pintype "passive"))
      (node (ref "R39") (pin "2") (pinfunction "2_2") (pintype "passive"))
      (node (ref "R8") (pin "1") (pinfunction "1_1") (pintype "passive"))
    )
    (net (code "58") (name "Net-(IC1B-IN-)") (class "Default")
      (node (ref "IC1") (pin "6") (pinfunction "IN-_6") (pintype "input"))
      (node (ref "R27") (pin "2") (pinfunction "2_2") (pintype "passive"))
      (node (ref "R36") (pin "2") (pinfunction "2_2") (pintype "passive"))
    )
    (net (code "59") (name "Net-(Q1-B)") (class "Default")
      (node (ref "Q1") (pin "1") (pinfunction "B_1") (pintype "passive"))
      (node (ref "Q2") (pin "1") (pinfunction "B_1") (pintype "passive"))
      (node (ref "R23") (pin "1") (pinfunction "1_1") (pintype "passive"))
    )
    (net (code "60") (name "Net-(Q9-G)") (class "Default")
      (node (ref "C86") (pin "2") (pinfunction "2_2") (pintype "passive"))
      (node (ref "Q9") (pin "1") (pinfunction "G_1") (pintype "passive"))
      (node (ref "R82") (pin "2") (pinfunction "2_2") (pintype "passive"))
      (node (ref "U3") (pin "1") (pinfunction "1B_1") (pintype "input"))
    )
    (net (code "61") (name "Net-(U3-2B)") (class "Default")
      (node (ref "R83") (pin "1") (pinfunction "1_1") (pintype "passive"))
      (node (ref "U3") (pin "2") (pinfunction "2B_2") (pintype "input"))
    )
    (net (code "62") (name "Net-(U3-GND)") (class "Default")
      (node (ref "F3") (pin "1") (pinfunction "1_1") (pintype "passive"))
      (node (ref "U3") (pin "8") (pinfunction "GND_8") (pintype "power_in"))
    )
    (net (code "63") (name "Net-(U4-BOOT_0)") (class "Default")
      (node (ref "R11") (pin "2") (pinfunction "2_2") (pintype "passive"))
      (node (ref "U4") (pin "44") (pinfunction "BOOT_0_44") (pintype "passive"))
    )
    (net (code "64") (name "Net-(U4-~{NRST})") (class "Default")
      (node (ref "C6") (pin "1") (pinfunction "1_1") (pintype "passive"))
      (node (ref "U4") (pin "7") (pinfunction "~{NRST}_7") (pintype "passive"))
    )
    (net (code "65") (name "VIN") (class "Default")
      (node (ref "P4") (pin "1") (pinfunction "1_1") (pintype "passive"))
      (node (ref "R67") (pin "1") (pinfunction "1_1") (pintype "passive"))
      (node (ref "U3") (pin "9") (pinfunction "COM_9") (pintype "passive"))
    )
    (net (code "66") (name "unconnected-(U4-PA2{slash}USART2_TX{slash}AIN2{slash}TIM2_CH3{slash}TIM15_CH1-Pad12)") (class "Default")
      (node (ref "U4") (pin "12") (pinfunction "PA2/USART2_TX/AIN2/TIM2_CH3/TIM15_CH1_12") (pintype "passive"))
    )
    (net (code "67") (name "unconnected-(U5-N{slash}C-Pad2)") (class "Default")
      (node (ref "U5") (pin "2") (pinfunction "N/C_2") (pintype "passive+no_connect"))
    )
    (net (code "68") (name "unconnected-(U5-RES-Pad10)") (class "Default")
      (node (ref "U5") (pin "10") (pinfunction "RES_10") (pintype "passive+no_connect"))
    )
  )
)
